# HyperRAM2.net
KiCad netlist of a schematic drawn in Altium Designer
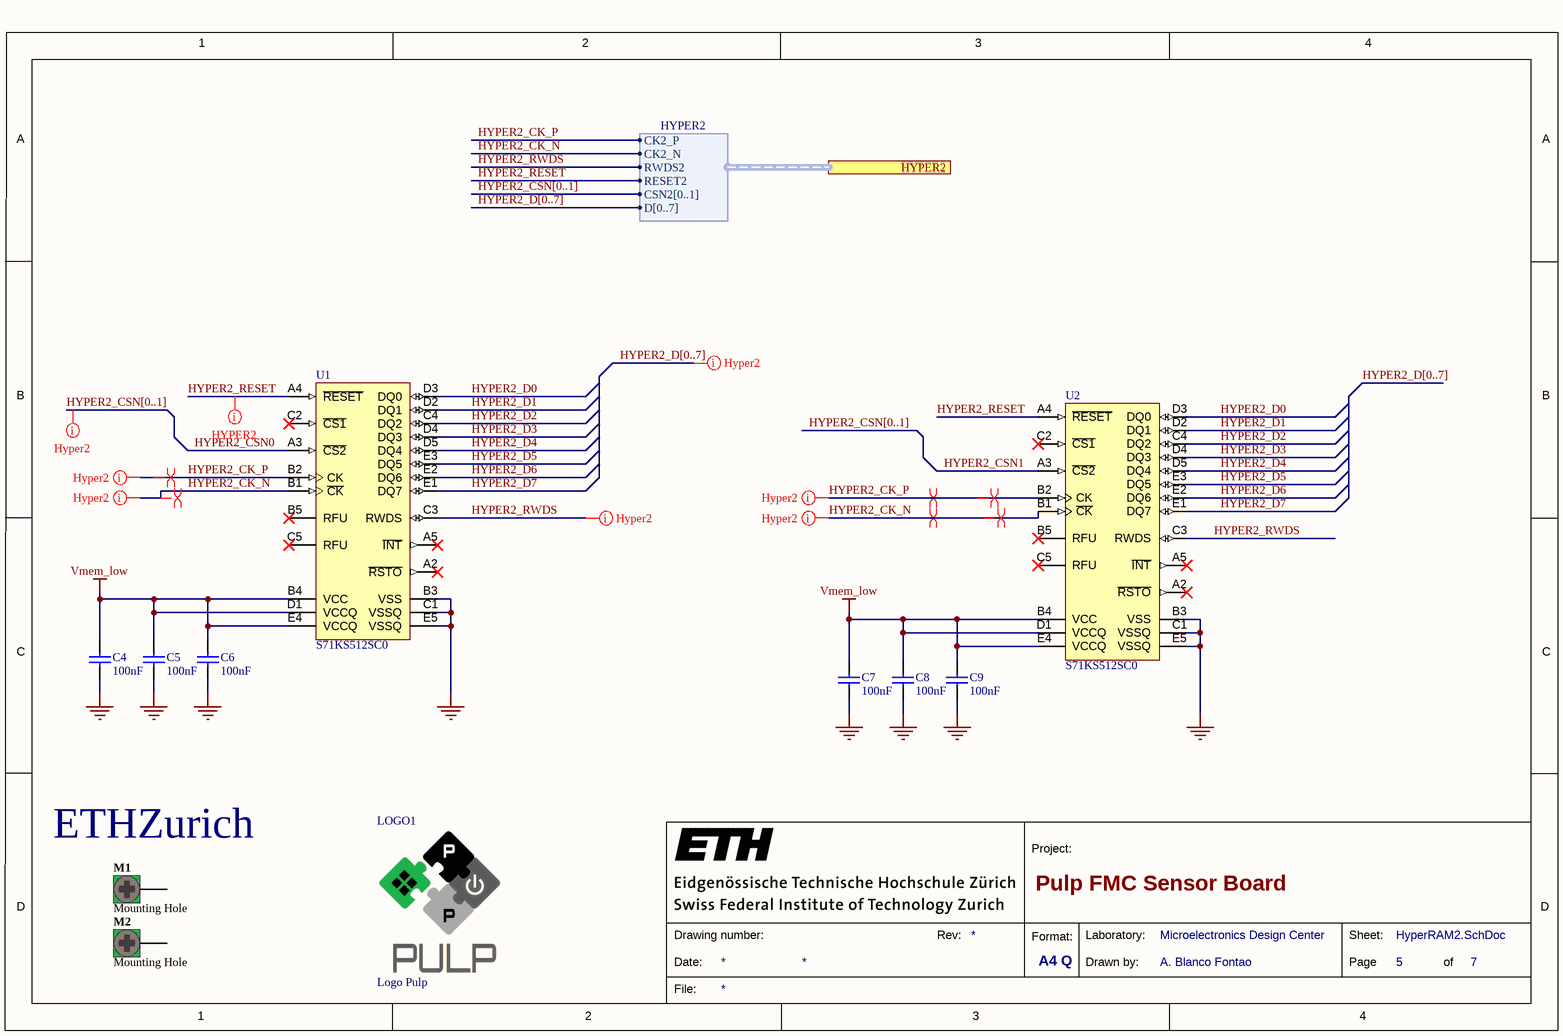
[diagram p0: HyperRAM2.SchDoc]

(export (version "E")
  (design (tool "Eeschema 10.0.6"))
  (components
    (comp (ref "A1")
      (value "Logo ETH Zurich")
      (footprint "eth-zurich_3mm")
      (libsource (lib "ETHZ Vault") (part "CMP-00038-1"))
    )
    (comp (ref "C4")
      (value "100nF")
      (footprint "CAPC0603(1608)100_N")
      (description "CAP 100nF 25V ±10% 0603 (1608 Metric) Thickness 1mm SMD")
      (fields (field (name "TOLERANCE") "Â±10%") (field (name "Comment") "CAP 100nF 25V 0603(1608)"))
      (libsource (lib "Altium Content Vault") (part "CMP-1035-02588-1"))
    )
    (comp (ref "C5")
      (value "100nF")
      (footprint "CAPC0603(1608)100_N")
      (description "CAP 100nF 25V ±10% 0603 (1608 Metric) Thickness 1mm SMD")
      (fields (field (name "TOLERANCE") "Â±10%") (field (name "Comment") "CAP 100nF 25V 0603(1608)"))
      (libsource (lib "Altium Content Vault") (part "CMP-1035-02588-1"))
    )
    (comp (ref "C6")
      (value "100nF")
      (footprint "CAPC0603(1608)100_N")
      (description "CAP 100nF 25V ±10% 0603 (1608 Metric) Thickness 1mm SMD")
      (fields (field (name "TOLERANCE") "Â±10%") (field (name "Comment") "CAP 100nF 25V 0603(1608)"))
      (libsource (lib "Altium Content Vault") (part "CMP-1035-02588-1"))
    )
    (comp (ref "C7")
      (value "100nF")
      (footprint "CAPC0603(1608)100_N")
      (description "CAP 100nF 25V ±10% 0603 (1608 Metric) Thickness 1mm SMD")
      (fields (field (name "TOLERANCE") "Â±10%") (field (name "Comment") "CAP 100nF 25V 0603(1608)"))
      (libsource (lib "Altium Content Vault") (part "CMP-1035-02588-1"))
    )
    (comp (ref "C8")
      (value "100nF")
      (footprint "CAPC0603(1608)100_N")
      (description "CAP 100nF 25V ±10% 0603 (1608 Metric) Thickness 1mm SMD")
      (fields (field (name "TOLERANCE") "Â±10%") (field (name "Comment") "CAP 100nF 25V 0603(1608)"))
      (libsource (lib "Altium Content Vault") (part "CMP-1035-02588-1"))
    )
    (comp (ref "C9")
      (value "100nF")
      (footprint "CAPC0603(1608)100_N")
      (description "CAP 100nF 25V ±10% 0603 (1608 Metric) Thickness 1mm SMD")
      (fields (field (name "TOLERANCE") "Â±10%") (field (name "Comment") "CAP 100nF 25V 0603(1608)"))
      (libsource (lib "Altium Content Vault") (part "CMP-1035-02588-1"))
    )
    (comp (ref "LOGO1")
      (value "Logo Pulp")
      (footprint "Logo Pulp")
      (description "4 Layers: only valid for layer stack as defined for the TestBoards")
      (libsource (lib "ETHZ Vault") (part "CMP-00145-1"))
    )
    (comp (ref "M1")
      (value "Mounting Hole")
      (footprint "Hole M3")
      (description "Mounting Hole, 7.2mm pad, 3.2mm plated hole")
      (libsource (lib "ETHZ Vault") (part "Hole"))
    )
    (comp (ref "M2")
      (value "Mounting Hole")
      (footprint "Hole M3")
      (description "Mounting Hole, 7.2mm pad, 3.2mm plated hole")
      (libsource (lib "ETHZ Vault") (part "Hole"))
    )
    (comp (ref "U1")
      (value "S71KS512SC0")
      (footprint "FBGA24_A-130")
      (description "IC 512MB FLASH 64MB DRAM 24FBGA")
      (fields (field (name "MANUFACTURER") "Cypress Semiconductor Corp"))
      (libsource (lib "Pulp FMC Sensor Board") (part "CMP-00514-1"))
    )
    (comp (ref "U2")
      (value "S71KS512SC0")
      (footprint "FBGA24_A-130")
      (description "IC 512MB FLASH 64MB DRAM 24FBGA")
      (fields (field (name "MANUFACTURER") "Cypress Semiconductor Corp"))
      (libsource (lib "Pulp FMC Sensor Board") (part "CMP-00514-1"))
    )
  )
  (nets
    (net (code "2") (name "/HYPER2_CK_N") (class "Default")
      (node (ref "U1") (pin "B1") (pinfunction "~{CK}_B1") (pintype "input"))
      (node (ref "U2") (pin "B1") (pinfunction "~{CK}_B1") (pintype "input"))
    )
    (net (code "3") (name "/HYPER2_CK_P") (class "Default")
      (node (ref "U1") (pin "B2") (pinfunction "CK_B2") (pintype "input"))
      (node (ref "U2") (pin "B2") (pinfunction "CK_B2") (pintype "input"))
    )
    (net (code "4") (name "/HYPER2_CSN0") (class "Default")
      (node (ref "U1") (pin "A3") (pinfunction "~{CS2}_A3") (pintype "input"))
    )
    (net (code "5") (name "/HYPER2_CSN1") (class "Default")
      (node (ref "U2") (pin "A3") (pinfunction "~{CS2}_A3") (pintype "input"))
    )
    (net (code "7") (name "/HYPER2_D0") (class "Default")
      (node (ref "U1") (pin "D3") (pinfunction "DQ0_D3") (pintype "bidirectional"))
      (node (ref "U2") (pin "D3") (pinfunction "DQ0_D3") (pintype "bidirectional"))
    )
    (net (code "8") (name "/HYPER2_D1") (class "Default")
      (node (ref "U1") (pin "D2") (pinfunction "DQ1_D2") (pintype "bidirectional"))
      (node (ref "U2") (pin "D2") (pinfunction "DQ1_D2") (pintype "bidirectional"))
    )
    (net (code "9") (name "/HYPER2_D2") (class "Default")
      (node (ref "U1") (pin "C4") (pinfunction "DQ2_C4") (pintype "bidirectional"))
      (node (ref "U2") (pin "C4") (pinfunction "DQ2_C4") (pintype "bidirectional"))
    )
    (net (code "10") (name "/HYPER2_D3") (class "Default")
      (node (ref "U1") (pin "D4") (pinfunction "DQ3_D4") (pintype "bidirectional"))
      (node (ref "U2") (pin "D4") (pinfunction "DQ3_D4") (pintype "bidirectional"))
    )
    (net (code "11") (name "/HYPER2_D4") (class "Default")
      (node (ref "U1") (pin "D5") (pinfunction "DQ4_D5") (pintype "bidirectional"))
      (node (ref "U2") (pin "D5") (pinfunction "DQ4_D5") (pintype "bidirectional"))
    )
    (net (code "12") (name "/HYPER2_D5") (class "Default")
      (node (ref "U1") (pin "E3") (pinfunction "DQ5_E3") (pintype "bidirectional"))
      (node (ref "U2") (pin "E3") (pinfunction "DQ5_E3") (pintype "bidirectional"))
    )
    (net (code "13") (name "/HYPER2_D6") (class "Default")
      (node (ref "U1") (pin "E2") (pinfunction "DQ6_E2") (pintype "bidirectional"))
      (node (ref "U2") (pin "E2") (pinfunction "DQ6_E2") (pintype "bidirectional"))
    )
    (net (code "14") (name "/HYPER2_D7") (class "Default")
      (node (ref "U1") (pin "E1") (pinfunction "DQ7_E1") (pintype "bidirectional"))
      (node (ref "U2") (pin "E1") (pinfunction "DQ7_E1") (pintype "bidirectional"))
    )
    (net (code "16") (name "/HYPER2_RESET") (class "Default")
      (node (ref "U1") (pin "A4") (pinfunction "~{RESET}_A4") (pintype "input"))
      (node (ref "U2") (pin "A4") (pinfunction "~{RESET}_A4") (pintype "input"))
    )
    (net (code "17") (name "/HYPER2_RWDS") (class "Default")
      (node (ref "U1") (pin "C3") (pinfunction "RWDS_C3") (pintype "bidirectional"))
      (node (ref "U2") (pin "C3") (pinfunction "RWDS_C3") (pintype "bidirectional"))
    )
    (net (code "19") (name "GND") (class "Default")
      (node (ref "C4") (pin "1") (pinfunction "1_1") (pintype "passive"))
      (node (ref "C5") (pin "1") (pinfunction "1_1") (pintype "passive"))
      (node (ref "C6") (pin "1") (pinfunction "1_1") (pintype "passive"))
      (node (ref "C7") (pin "1") (pinfunction "1_1") (pintype "passive"))
      (node (ref "C8") (pin "1") (pinfunction "1_1") (pintype "passive"))
      (node (ref "C9") (pin "1") (pinfunction "1_1") (pintype "passive"))
      (node (ref "U1") (pin "B3") (pinfunction "VSS_B3") (pintype "power_in"))
      (node (ref "U1") (pin "C1") (pinfunction "VSSQ_C1") (pintype "power_in"))
      (node (ref "U1") (pin "E5") (pinfunction "VSSQ_E5") (pintype "power_in"))
      (node (ref "U2") (pin "B3") (pinfunction "VSS_B3") (pintype "power_in"))
      (node (ref "U2") (pin "C1") (pinfunction "VSSQ_C1") (pintype "power_in"))
      (node (ref "U2") (pin "E5") (pinfunction "VSSQ_E5") (pintype "power_in"))
    )
    (net (code "20") (name "Vmem_low") (class "Default")
      (node (ref "C4") (pin "2") (pinfunction "2_2") (pintype "passive"))
      (node (ref "C5") (pin "2") (pinfunction "2_2") (pintype "passive"))
      (node (ref "C6") (pin "2") (pinfunction "2_2") (pintype "passive"))
      (node (ref "C7") (pin "2") (pinfunction "2_2") (pintype "passive"))
      (node (ref "C8") (pin "2") (pinfunction "2_2") (pintype "passive"))
      (node (ref "C9") (pin "2") (pinfunction "2_2") (pintype "passive"))
      (node (ref "U1") (pin "B4") (pinfunction "VCC_B4") (pintype "power_in"))
      (node (ref "U1") (pin "D1") (pinfunction "VCCQ_D1") (pintype "power_in"))
      (node (ref "U1") (pin "E4") (pinfunction "VCCQ_E4") (pintype "power_in"))
      (node (ref "U2") (pin "B4") (pinfunction "VCC_B4") (pintype "power_in"))
      (node (ref "U2") (pin "D1") (pinfunction "VCCQ_D1") (pintype "power_in"))
      (node (ref "U2") (pin "E4") (pinfunction "VCCQ_E4") (pintype "power_in"))
    )
    (net (code "21") (name "unconnected-(M1-Pad1)") (class "Default")
      (node (ref "M1") (pin "1") (pinfunction "1_1") (pintype "passive"))
    )
    (net (code "22") (name "unconnected-(M2-Pad1)") (class "Default")
      (node (ref "M2") (pin "1") (pinfunction "1_1") (pintype "passive"))
    )
    (net (code "23") (name "unconnected-(U1-RFU-PadB5)") (class "Default")
      (node (ref "U1") (pin "B5") (pinfunction "RFU_B5") (pintype "passive+no_connect"))
    )
    (net (code "24") (name "unconnected-(U1-RFU-PadC5)") (class "Default")
      (node (ref "U1") (pin "C5") (pinfunction "RFU_C5") (pintype "passive+no_connect"))
    )
    (net (code "25") (name "unconnected-(U1-~{CS1}-PadC2)") (class "Default")
      (node (ref "U1") (pin "C2") (pinfunction "~{CS1}_C2") (pintype "input+no_connect"))
    )
    (net (code "26") (name "unconnected-(U1-~{INT}-PadA5)") (class "Default")
      (node (ref "U1") (pin "A5") (pinfunction "~{INT}_A5") (pintype "output+no_connect"))
    )
    (net (code "27") (name "unconnected-(U1-~{RSTO}-PadA2)") (class "Default")
      (node (ref "U1") (pin "A2") (pinfunction "~{RSTO}_A2") (pintype "output+no_connect"))
    )
    (net (code "28") (name "unconnected-(U2-RFU-PadB5)") (class "Default")
      (node (ref "U2") (pin "B5") (pinfunction "RFU_B5") (pintype "passive+no_connect"))
    )
    (net (code "29") (name "unconnected-(U2-RFU-PadC5)") (class "Default")
      (node (ref "U2") (pin "C5") (pinfunction "RFU_C5") (pintype "passive+no_connect"))
    )
    (net (code "30") (name "unconnected-(U2-~{CS1}-PadC2)") (class "Default")
      (node (ref "U2") (pin "C2") (pinfunction "~{CS1}_C2") (pintype "input+no_connect"))
    )
    (net (code "31") (name "unconnected-(U2-~{INT}-PadA5)") (class "Default")
      (node (ref "U2") (pin "A5") (pinfunction "~{INT}_A5") (pintype "output+no_connect"))
    )
    (net (code "32") (name "unconnected-(U2-~{RSTO}-PadA2)") (class "Default")
      (node (ref "U2") (pin "A2") (pinfunction "~{RSTO}_A2") (pintype "output+no_connect"))
    )
  )
)
